# OvenPi.net
KiCad netlist of a schematic drawn in Altium Designer
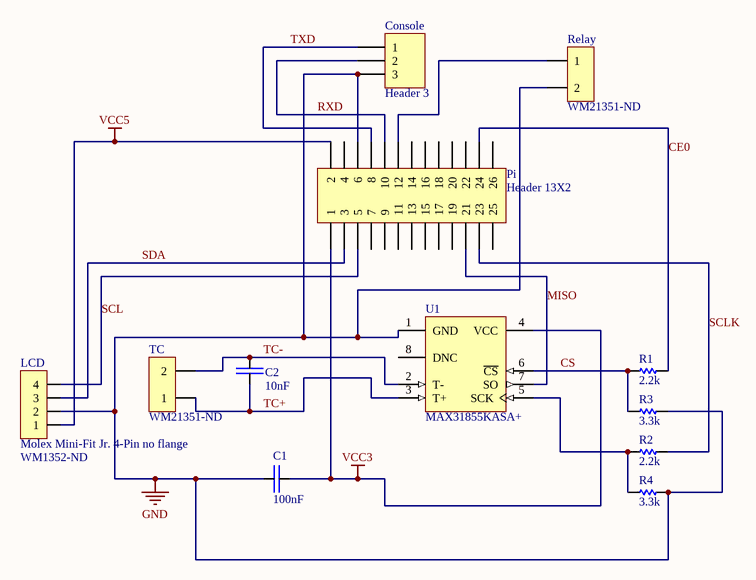
[diagram p0: OvenPi.SchDoc]

(export (version "E")
  (design (tool "Eeschema 10.0.6"))
  (components
    (comp (ref "C1")
      (value "100nF")
      (footprint "0603_B")
      (description "1uF Ceramic SMT 0603")
      (fields (field (name "Comment") "GRM188F51E105ZA12D"))
      (libsource (lib "Capacitors") (part "GRM188F51E105ZA12D"))
    )
    (comp (ref "C2")
      (value "10nF")
      (footprint "0603_B")
      (description "1uF Ceramic SMT 0603")
      (fields (field (name "Comment") "GRM188F51E105ZA12D"))
      (libsource (lib "Capacitors") (part "GRM188F51E105ZA12D"))
    )
    (comp (ref "Console")
      (value "Header 3")
      (footprint "HDR1X3")
      (description "Header, 3-Pin")
      (fields (field (name "PUBLISHER") "Altium Limited"))
      (libsource (lib "Miscellaneous Connectors") (part "Header 3"))
    )
    (comp (ref "LCD")
      (value "Molex Mini-Fit Jr. 4-Pin no flange")
      (footprint "Molex Mini-Fit Jr. 4-Pin - no flange")
      (description "4-Pin Molex Mini-Fit Jr. Header")
      (fields
        (field (name "MANUFACTURER") "Molex")
        (field (name "MANUFACTURER PART NUMBER") "0039301040")
        (field (name "SUPPLIER PART NUMBER 1") "WM1352-ND")
        (field (name "DRAWN BY") "Aaron Mills")
      )
      (libsource (lib "Interconnects") (part "Molex Mini-Fit Jr. 4-Pin"))
    )
    (comp (ref "Pi")
      (value "Header 13X2")
      (footprint "HDR2X13")
      (description "Header, 13-Pin, Dual row")
      (fields (field (name "PUBLISHER") "Altium Limited"))
      (libsource (lib "Miscellaneous Connectors") (part "Header 13X2"))
    )
    (comp (ref "R1")
      (value "2.2k")
      (footprint "0603_B")
      (description "0603 2.4kOhm resistor")
      (fields (field (name "Comment") "CRCW06032K40JNEA"))
      (libsource (lib "Resistors") (part "CRCW06032K40JNEA"))
    )
    (comp (ref "R2")
      (value "2.2k")
      (footprint "0603_B")
      (description "0603 2.4kOhm resistor")
      (fields (field (name "Comment") "CRCW06032K40JNEA"))
      (libsource (lib "Resistors") (part "CRCW06032K40JNEA"))
    )
    (comp (ref "R3")
      (value "3.3k")
      (footprint "0603_B")
      (description "0603 2.4kOhm resistor")
      (fields (field (name "Comment") "CRCW06032K40JNEA"))
      (libsource (lib "Resistors") (part "CRCW06032K40JNEA"))
    )
    (comp (ref "R4")
      (value "3.3k")
      (footprint "0603_B")
      (description "0603 2.4kOhm resistor")
      (fields (field (name "Comment") "CRCW06032K40JNEA"))
      (libsource (lib "Resistors") (part "CRCW06032K40JNEA"))
    )
    (comp (ref "Relay")
      (value "Mini-Fit Jr. 2-pin")
      (footprint "Mini-Fit Jr. 2")
      (description "Mini-Fit Jr. 2-pin Right Angle")
      (fields
        (field (name "MANUFACTURER") "Molex Inc")
        (field (name "MANUFACTURER PART NUMBER") "0039300020")
        (field (name "SUPPLIER PART NUMBER 1") "WM21351-ND")
      )
      (libsource (lib "") (part "Mini-Fit Jr. 2-pin_1"))
    )
    (comp (ref "TC")
      (value "Mini-Fit Jr. 2-pin")
      (footprint "Mini-Fit Jr. 2")
      (description "Mini-Fit Jr. 2-pin Right Angle")
      (fields
        (field (name "MANUFACTURER") "Molex Inc")
        (field (name "MANUFACTURER PART NUMBER") "0039300020")
        (field (name "SUPPLIER PART NUMBER 1") "WM21351-ND")
      )
      (libsource (lib "Interconnects") (part "Mini-Fit Jr. 2-pin"))
    )
    (comp (ref "U1")
      (value "MAX31855KASA+")
      (footprint "MAXM-S8+4_N")
      (fields (field (name "GENERIC PART NUMBER") "MAX31855"))
      (libsource (lib "Maxim Sensors") (part "MAX31855KASA+"))
    )
  )
  (nets
    (net (code "1") (name "/CE0") (class "Default")
      (node (ref "Pi") (pin "24") (pinfunction "24_24") (pintype "passive"))
      (node (ref "R1") (pin "2") (pinfunction "2_2") (pintype "passive"))
    )
    (net (code "2") (name "/CS") (class "Default")
      (node (ref "R1") (pin "1") (pinfunction "1_1") (pintype "passive"))
      (node (ref "R3") (pin "1") (pinfunction "1_1") (pintype "passive"))
      (node (ref "U1") (pin "6") (pinfunction "~{CS}_6") (pintype "input"))
    )
    (net (code "3") (name "/MISO") (class "Default")
      (node (ref "Pi") (pin "21") (pinfunction "21_21") (pintype "passive"))
      (node (ref "U1") (pin "7") (pinfunction "SO_7") (pintype "output"))
    )
    (net (code "4") (name "/RXD") (class "Default")
      (node (ref "Console") (pin "2") (pinfunction "2_2") (pintype "passive"))
      (node (ref "Pi") (pin "10") (pinfunction "10_10") (pintype "passive"))
    )
    (net (code "5") (name "/SCL") (class "Default")
      (node (ref "LCD") (pin "4") (pinfunction "4_4") (pintype "passive"))
      (node (ref "Pi") (pin "5") (pinfunction "5_5") (pintype "passive"))
    )
    (net (code "6") (name "/SCLK") (class "Default")
      (node (ref "Pi") (pin "23") (pinfunction "23_23") (pintype "passive"))
      (node (ref "R2") (pin "2") (pinfunction "2_2") (pintype "passive"))
    )
    (net (code "7") (name "/SDA") (class "Default")
      (node (ref "LCD") (pin "3") (pinfunction "3_3") (pintype "passive"))
      (node (ref "Pi") (pin "3") (pinfunction "3_3") (pintype "passive"))
    )
    (net (code "8") (name "/TC+") (class "Default")
      (node (ref "C2") (pin "2") (pinfunction "2_2") (pintype "passive"))
      (node (ref "TC") (pin "1") (pinfunction "1_1") (pintype "passive"))
      (node (ref "U1") (pin "3") (pinfunction "T+_3") (pintype "input"))
    )
    (net (code "9") (name "/TC-") (class "Default")
      (node (ref "C2") (pin "1") (pinfunction "1_1") (pintype "passive"))
      (node (ref "TC") (pin "2") (pinfunction "2_2") (pintype "passive"))
      (node (ref "U1") (pin "2") (pinfunction "T-_2") (pintype "input"))
    )
    (net (code "10") (name "/TXD") (class "Default")
      (node (ref "Console") (pin "1") (pinfunction "1_1") (pintype "passive"))
      (node (ref "Pi") (pin "8") (pinfunction "8_8") (pintype "passive"))
    )
    (net (code "11") (name "GND") (class "Default")
      (node (ref "C1") (pin "1") (pinfunction "1_1") (pintype "passive"))
      (node (ref "Console") (pin "3") (pinfunction "3_3") (pintype "passive"))
      (node (ref "LCD") (pin "2") (pinfunction "2_2") (pintype "passive"))
      (node (ref "Pi") (pin "6") (pinfunction "6_6") (pintype "passive"))
      (node (ref "R3") (pin "2") (pinfunction "2_2") (pintype "passive"))
      (node (ref "R4") (pin "2") (pinfunction "2_2") (pintype "passive"))
      (node (ref "Relay") (pin "2") (pinfunction "2_2") (pintype "passive"))
      (node (ref "U1") (pin "1") (pinfunction "GND_1") (pintype "power_in"))
    )
    (net (code "12") (name "Net-(Pi-Pad12)") (class "Default")
      (node (ref "Pi") (pin "12") (pinfunction "12_12") (pintype "passive"))
      (node (ref "Relay") (pin "1") (pinfunction "1_1") (pintype "passive"))
    )
    (net (code "13") (name "Net-(U1-SCK)") (class "Default")
      (node (ref "R2") (pin "1") (pinfunction "1_1") (pintype "passive"))
      (node (ref "R4") (pin "1") (pinfunction "1_1") (pintype "passive"))
      (node (ref "U1") (pin "5") (pinfunction "SCK_5") (pintype "input"))
    )
    (net (code "14") (name "VCC3") (class "Default")
      (node (ref "C1") (pin "2") (pinfunction "2_2") (pintype "passive"))
      (node (ref "Pi") (pin "1") (pinfunction "1_1") (pintype "passive"))
      (node (ref "U1") (pin "4") (pinfunction "VCC_4") (pintype "power_in"))
    )
    (net (code "15") (name "VCC5") (class "Default")
      (node (ref "LCD") (pin "1") (pinfunction "1_1") (pintype "passive"))
      (node (ref "Pi") (pin "2") (pinfunction "2_2") (pintype "passive"))
    )
    (net (code "16") (name "unconnected-(Pi-Pad4)") (class "Default")
      (node (ref "Pi") (pin "4") (pinfunction "4_4") (pintype "passive"))
    )
    (net (code "17") (name "unconnected-(Pi-Pad7)") (class "Default")
      (node (ref "Pi") (pin "7") (pinfunction "7_7") (pintype "passive"))
    )
    (net (code "18") (name "unconnected-(Pi-Pad9)") (class "Default")
      (node (ref "Pi") (pin "9") (pinfunction "9_9") (pintype "passive"))
    )
    (net (code "19") (name "unconnected-(Pi-Pad11)") (class "Default")
      (node (ref "Pi") (pin "11") (pinfunction "11_11") (pintype "passive"))
    )
    (net (code "20") (name "unconnected-(Pi-Pad13)") (class "Default")
      (node (ref "Pi") (pin "13") (pinfunction "13_13") (pintype "passive"))
    )
    (net (code "21") (name "unconnected-(Pi-Pad14)") (class "Default")
      (node (ref "Pi") (pin "14") (pinfunction "14_14") (pintype "passive"))
    )
    (net (code "22") (name "unconnected-(Pi-Pad15)") (class "Default")
      (node (ref "Pi") (pin "15") (pinfunction "15_15") (pintype "passive"))
    )
    (net (code "23") (name "unconnected-(Pi-Pad16)") (class "Default")
      (node (ref "Pi") (pin "16") (pinfunction "16_16") (pintype "passive"))
    )
    (net (code "24") (name "unconnected-(Pi-Pad17)") (class "Default")
      (node (ref "Pi") (pin "17") (pinfunction "17_17") (pintype "passive"))
    )
    (net (code "25") (name "unconnected-(Pi-Pad18)") (class "Default")
      (node (ref "Pi") (pin "18") (pinfunction "18_18") (pintype "passive"))
    )
    (net (code "26") (name "unconnected-(Pi-Pad19)") (class "Default")
      (node (ref "Pi") (pin "19") (pinfunction "19_19") (pintype "passive"))
    )
    (net (code "27") (name "unconnected-(Pi-Pad20)") (class "Default")
      (node (ref "Pi") (pin "20") (pinfunction "20_20") (pintype "passive"))
    )
    (net (code "28") (name "unconnected-(Pi-Pad22)") (class "Default")
      (node (ref "Pi") (pin "22") (pinfunction "22_22") (pintype "passive"))
    )
    (net (code "29") (name "unconnected-(Pi-Pad25)") (class "Default")
      (node (ref "Pi") (pin "25") (pinfunction "25_25") (pintype "passive"))
    )
    (net (code "30") (name "unconnected-(Pi-Pad26)") (class "Default")
      (node (ref "Pi") (pin "26") (pinfunction "26_26") (pintype "passive"))
    )
    (net (code "31") (name "unconnected-(U1-DNC-Pad8)") (class "Default")
      (node (ref "U1") (pin "8") (pinfunction "DNC_8") (pintype "passive"))
    )
  )
)
